# atxpsudevboard_0-1b.net
KiCad netlist of a schematic drawn in EAGLE
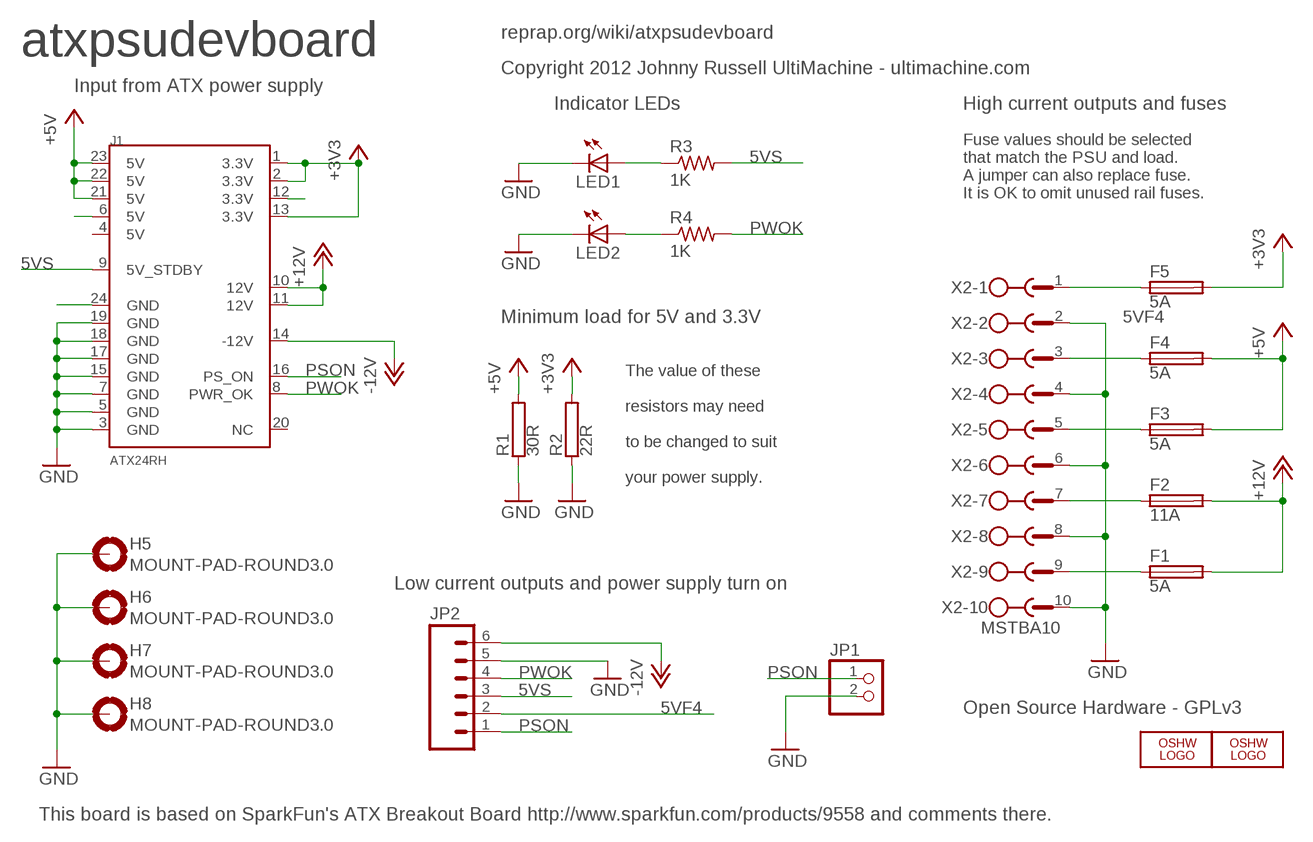
[diagram p0: schematic, sheet 1]

(export (version "E")
  (design (tool "Eeschema 10.0.6"))
  (components
    (comp (ref "F1")
      (value "5A")
      (footprint "eagle-import:MFR1100")
      (libsource (lib "eagle-import") (part "PTCFUSEMFR1100"))
    )
    (comp (ref "F2")
      (value "11A")
      (footprint "eagle-import:MFR1100")
      (libsource (lib "eagle-import") (part "PTCFUSEMFR1100"))
    )
    (comp (ref "F3")
      (value "5A")
      (footprint "eagle-import:MFR1100")
      (libsource (lib "eagle-import") (part "PTCFUSEMFR1100"))
    )
    (comp (ref "F4")
      (value "5A")
      (footprint "eagle-import:MFR1100")
      (libsource (lib "eagle-import") (part "PTCFUSEMFR1100"))
    )
    (comp (ref "F5")
      (value "5A")
      (footprint "eagle-import:MFR1100")
      (libsource (lib "eagle-import") (part "PTCFUSEMFR1100"))
    )
    (comp (ref "H5")
      (value "MOUNT-PAD-ROUND3.0")
      (footprint "eagle-import:3,0-PAD")
      (libsource (lib "eagle-import") (part "MOUNT-PAD-ROUND3.0"))
    )
    (comp (ref "H6")
      (value "MOUNT-PAD-ROUND3.0")
      (footprint "eagle-import:3,0-PAD")
      (libsource (lib "eagle-import") (part "MOUNT-PAD-ROUND3.0"))
    )
    (comp (ref "H7")
      (value "MOUNT-PAD-ROUND3.0")
      (footprint "eagle-import:3,0-PAD")
      (libsource (lib "eagle-import") (part "MOUNT-PAD-ROUND3.0"))
    )
    (comp (ref "H8")
      (value "MOUNT-PAD-ROUND3.0")
      (footprint "eagle-import:3,0-PAD")
      (libsource (lib "eagle-import") (part "MOUNT-PAD-ROUND3.0"))
    )
    (comp (ref "J1")
      (value "ATX24RH")
      (footprint "eagle-import:ATX24_RIGHT_ANGLE")
      (libsource (lib "eagle-import") (part "ATX24RH"))
    )
    (comp (ref "JP1")
      (value "PINHD-1X2")
      (footprint "eagle-import:1X02")
      (libsource (lib "eagle-import") (part "PINHD-1X2"))
    )
    (comp (ref "JP2")
      (value "M06LONGPADS")
      (footprint "eagle-import:1X06_LONGPADS")
      (libsource (lib "eagle-import") (part "M06LONGPADS"))
    )
    (comp (ref "LED1")
      (value "LED3MM")
      (footprint "eagle-import:LED3MM")
      (libsource (lib "eagle-import") (part "LED3MM"))
    )
    (comp (ref "LED2")
      (value "LED3MM")
      (footprint "eagle-import:LED3MM")
      (libsource (lib "eagle-import") (part "LED3MM"))
    )
    (comp (ref "LOGO1")
      (value "OSHW_LOGO_FILLX0100-NT")
      (footprint "eagle-import:OSHW_FILLX100_NOTEXT")
      (libsource (lib "eagle-import") (part "OSHW_LOGO_FILLX0100-NT"))
    )
    (comp (ref "LOGO2")
      (value "OSHW_LOGO_FILLX0200-NT")
      (footprint "eagle-import:OSHW_FILLX200_NOTEXT")
      (libsource (lib "eagle-import") (part "OSHW_LOGO_FILLX0200-NT"))
    )
    (comp (ref "R1")
      (value "30R")
      (footprint "eagle-import:HPS923")
      (libsource (lib "eagle-import") (part "RHPS923"))
    )
    (comp (ref "R2")
      (value "22R")
      (footprint "eagle-import:CA4050")
      (libsource (lib "eagle-import") (part "RCA4050"))
    )
    (comp (ref "R3")
      (value "1K")
      (footprint "eagle-import:0207_7")
      (libsource (lib "eagle-import") (part "R-US_0207/7"))
    )
    (comp (ref "R4")
      (value "1K")
      (footprint "eagle-import:0207_7")
      (libsource (lib "eagle-import") (part "R-US_0207/7"))
    )
    (comp (ref "X2")
      (value "MSTBA10")
      (footprint "eagle-import:MSTBA10")
      (fields (field (name "MF") "FARNELL") (field (name "MPN") "1757323"))
      (libsource (lib "eagle-import") (part "MSTBA10"))
    )
  )
  (nets
    (net (code "1") (name "+3V3") (class "Default")
      (node (ref "F5") (pin "2") (pinfunction "2_2") (pintype "passive"))
      (node (ref "J1") (pin "1") (pinfunction "3.3V_1") (pintype "bidirectional"))
      (node (ref "J1") (pin "13") (pinfunction "3.3V_13") (pintype "bidirectional"))
      (node (ref "J1") (pin "2") (pinfunction "3.3V_2") (pintype "bidirectional"))
      (node (ref "R2") (pin "2") (pinfunction "2_2") (pintype "passive"))
    )
    (net (code "2") (name "+5V") (class "Default")
      (node (ref "F3") (pin "2") (pinfunction "2_2") (pintype "passive"))
      (node (ref "F4") (pin "2") (pinfunction "2_2") (pintype "passive"))
      (node (ref "J1") (pin "21") (pinfunction "5V_21") (pintype "bidirectional"))
      (node (ref "J1") (pin "22") (pinfunction "5V_22") (pintype "bidirectional"))
      (node (ref "J1") (pin "23") (pinfunction "5V_23") (pintype "bidirectional"))
      (node (ref "R1") (pin "2") (pinfunction "2_2") (pintype "passive"))
    )
    (net (code "3") (name "+12V") (class "Default")
      (node (ref "F1") (pin "2") (pinfunction "2_2") (pintype "passive"))
      (node (ref "F2") (pin "2") (pinfunction "2_2") (pintype "passive"))
      (node (ref "J1") (pin "10") (pinfunction "12V_10") (pintype "bidirectional"))
      (node (ref "J1") (pin "11") (pinfunction "12V_11") (pintype "bidirectional"))
    )
    (net (code "4") (name "-12V") (class "Default")
      (node (ref "J1") (pin "14") (pinfunction "-12V_14") (pintype "bidirectional"))
      (node (ref "JP2") (pin "6") (pinfunction "6_6") (pintype "passive"))
    )
    (net (code "5") (name "/5VF4") (class "Default")
      (node (ref "F4") (pin "1") (pinfunction "1_1") (pintype "passive"))
      (node (ref "JP2") (pin "2") (pinfunction "2_2") (pintype "passive"))
      (node (ref "X2") (pin "3") (pinfunction "1_3") (pintype "passive"))
    )
    (net (code "6") (name "/5VS") (class "Default")
      (node (ref "J1") (pin "9") (pinfunction "5V_STDBY_9") (pintype "bidirectional"))
      (node (ref "JP2") (pin "3") (pinfunction "3_3") (pintype "passive"))
      (node (ref "R3") (pin "2") (pinfunction "2_2") (pintype "passive"))
    )
    (net (code "7") (name "/PSON") (class "Default")
      (node (ref "J1") (pin "16") (pinfunction "PS_ON_16") (pintype "bidirectional"))
      (node (ref "JP1") (pin "1") (pinfunction "1_1") (pintype "passive"))
      (node (ref "JP2") (pin "1") (pinfunction "1_1") (pintype "passive"))
    )
    (net (code "8") (name "/PWOK") (class "Default")
      (node (ref "J1") (pin "8") (pinfunction "PWR_OK_8") (pintype "bidirectional"))
      (node (ref "JP2") (pin "4") (pinfunction "4_4") (pintype "passive"))
      (node (ref "R4") (pin "2") (pinfunction "2_2") (pintype "passive"))
    )
    (net (code "9") (name "GND") (class "Default")
      (node (ref "H5") (pin "B3,0") (pinfunction "MOUNT_B3,0") (pintype "passive"))
      (node (ref "H6") (pin "B3,0") (pinfunction "MOUNT_B3,0") (pintype "passive"))
      (node (ref "H7") (pin "B3,0") (pinfunction "MOUNT_B3,0") (pintype "passive"))
      (node (ref "H8") (pin "B3,0") (pinfunction "MOUNT_B3,0") (pintype "passive"))
      (node (ref "J1") (pin "15") (pinfunction "GND_15") (pintype "bidirectional"))
      (node (ref "J1") (pin "17") (pinfunction "GND_17") (pintype "bidirectional"))
      (node (ref "J1") (pin "18") (pinfunction "GND_18") (pintype "bidirectional"))
      (node (ref "J1") (pin "19") (pinfunction "GND_19") (pintype "bidirectional"))
      (node (ref "J1") (pin "3") (pinfunction "GND_3") (pintype "bidirectional"))
      (node (ref "J1") (pin "5") (pinfunction "GND_5") (pintype "bidirectional"))
      (node (ref "J1") (pin "7") (pinfunction "GND_7") (pintype "bidirectional"))
      (node (ref "JP1") (pin "2") (pinfunction "2_2") (pintype "passive"))
      (node (ref "JP2") (pin "5") (pinfunction "5_5") (pintype "passive"))
      (node (ref "LED1") (pin "K") (pinfunction "C_K") (pintype "passive"))
      (node (ref "LED2") (pin "K") (pinfunction "C_K") (pintype "passive"))
      (node (ref "R1") (pin "1") (pinfunction "1_1") (pintype "passive"))
      (node (ref "R2") (pin "1") (pinfunction "1_1") (pintype "passive"))
      (node (ref "X2") (pin "10") (pinfunction "1_10") (pintype "passive"))
      (node (ref "X2") (pin "2") (pinfunction "1_2") (pintype "passive"))
      (node (ref "X2") (pin "4") (pinfunction "1_4") (pintype "passive"))
      (node (ref "X2") (pin "6") (pinfunction "1_6") (pintype "passive"))
      (node (ref "X2") (pin "8") (pinfunction "1_8") (pintype "passive"))
    )
    (net (code "10") (name "Net-(F5-Pad1)") (class "Default")
      (node (ref "F5") (pin "1") (pinfunction "1_1") (pintype "passive"))
      (node (ref "X2") (pin "1") (pinfunction "1_1") (pintype "passive"))
    )
    (net (code "11") (name "Net-(LED1-PadA)") (class "Default")
      (node (ref "LED1") (pin "A") (pinfunction "A_A") (pintype "passive"))
      (node (ref "R3") (pin "1") (pinfunction "1_1") (pintype "passive"))
    )
    (net (code "12") (name "Net-(LED2-PadA)") (class "Default")
      (node (ref "LED2") (pin "A") (pinfunction "A_A") (pintype "passive"))
      (node (ref "R4") (pin "1") (pinfunction "1_1") (pintype "passive"))
    )
    (net (code "13") (name "Net-(X2F-1)") (class "Default")
      (node (ref "F3") (pin "1") (pinfunction "1_1") (pintype "passive"))
      (node (ref "X2") (pin "5") (pinfunction "1_5") (pintype "passive"))
    )
    (net (code "14") (name "Net-(X2H-1)") (class "Default")
      (node (ref "F2") (pin "1") (pinfunction "1_1") (pintype "passive"))
      (node (ref "X2") (pin "7") (pinfunction "1_7") (pintype "passive"))
    )
    (net (code "15") (name "Net-(X2J-1)") (class "Default")
      (node (ref "F1") (pin "1") (pinfunction "1_1") (pintype "passive"))
      (node (ref "X2") (pin "9") (pinfunction "1_9") (pintype "passive"))
    )
    (net (code "16") (name "unconnected-(J1-3.3V-Pad12)") (class "Default")
      (node (ref "J1") (pin "12") (pinfunction "3.3V_12") (pintype "bidirectional"))
    )
    (net (code "17") (name "unconnected-(J1-5V-Pad4)") (class "Default")
      (node (ref "J1") (pin "4") (pinfunction "5V_4") (pintype "bidirectional"))
    )
    (net (code "18") (name "unconnected-(J1-5V-Pad6)") (class "Default")
      (node (ref "J1") (pin "6") (pinfunction "5V_6") (pintype "bidirectional"))
    )
    (net (code "19") (name "unconnected-(J1-GND-Pad24)") (class "Default")
      (node (ref "J1") (pin "24") (pinfunction "GND_24") (pintype "bidirectional"))
    )
    (net (code "20") (name "unconnected-(J1-NC-Pad20)") (class "Default")
      (node (ref "J1") (pin "20") (pinfunction "NC_20") (pintype "bidirectional"))
    )
  )
)
